# input.net
KiCad netlist of a schematic drawn in Altium Designer
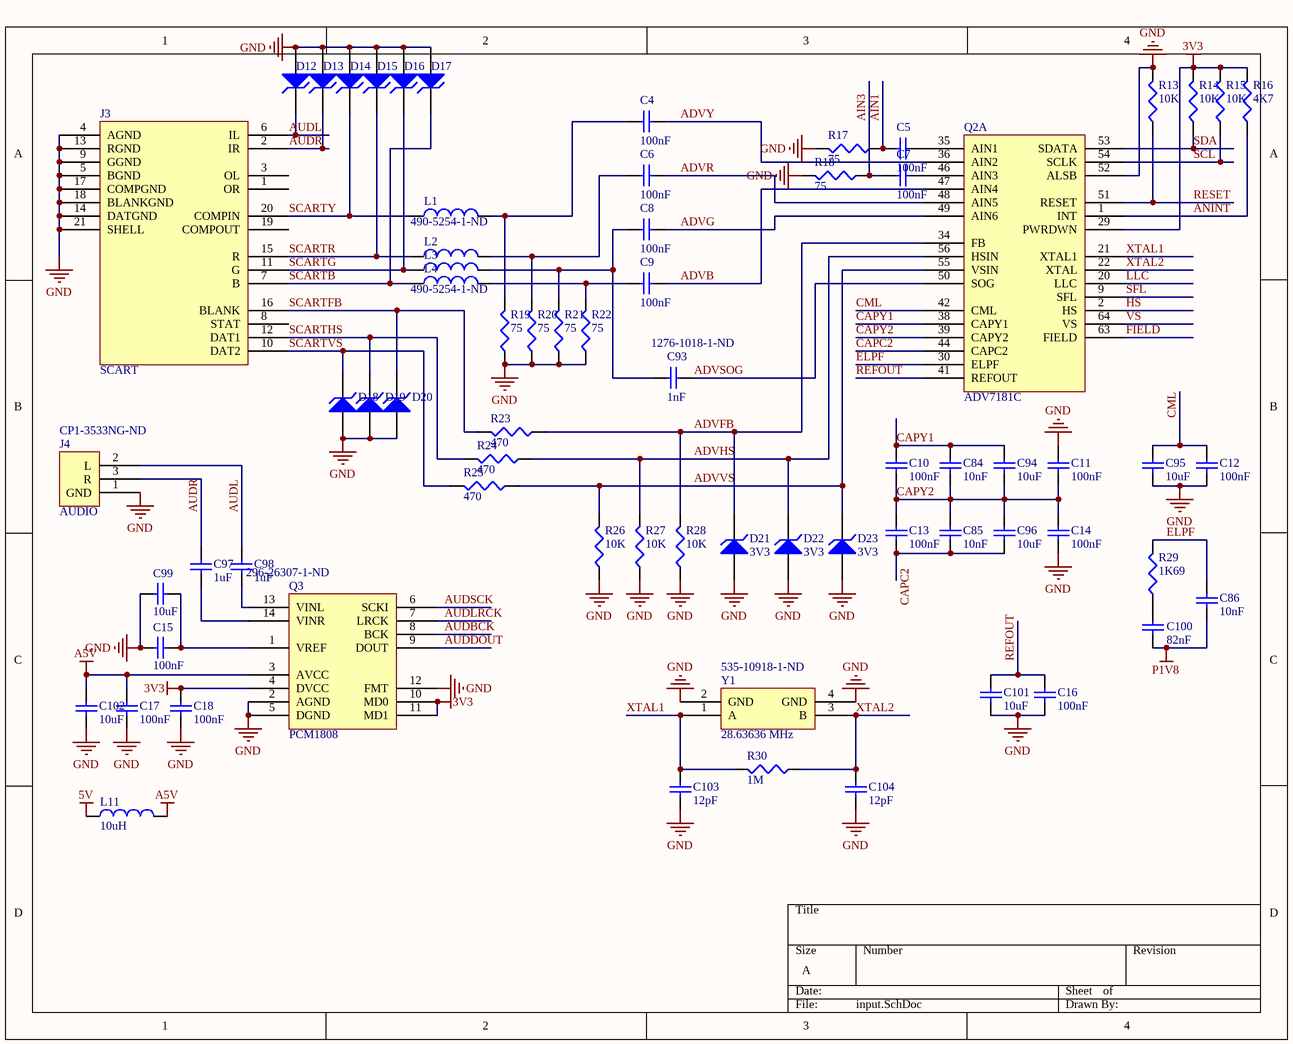
[diagram p0: input.SchDoc]

(export (version "E")
  (design (tool "Eeschema 10.0.6"))
  (components
    (comp (ref "C4")
      (value "100nF")
      (footprint "CAPC1005X06L")
      (description "Capacitor")
      (fields (field (name "Comment") "Cap") (field (name "PUBLISHER") "Altium Limited"))
      (libsource (lib "Miscellaneous Devices") (part "Cap"))
    )
    (comp (ref "C5")
      (value "100nF")
      (footprint "CAPC1005X06L")
      (description "Capacitor")
      (fields (field (name "Comment") "Cap") (field (name "PUBLISHER") "Altium Limited"))
      (libsource (lib "Miscellaneous Devices") (part "Cap"))
    )
    (comp (ref "C6")
      (value "100nF")
      (footprint "CAPC1005X06L")
      (description "Capacitor")
      (fields (field (name "Comment") "Cap") (field (name "PUBLISHER") "Altium Limited"))
      (libsource (lib "Miscellaneous Devices") (part "Cap"))
    )
    (comp (ref "C7")
      (value "100nF")
      (footprint "CAPC1005X06L")
      (description "Capacitor")
      (fields (field (name "Comment") "Cap") (field (name "PUBLISHER") "Altium Limited"))
      (libsource (lib "Miscellaneous Devices") (part "Cap"))
    )
    (comp (ref "C8")
      (value "100nF")
      (footprint "CAPC1005X06L")
      (description "Capacitor")
      (fields (field (name "Comment") "Cap") (field (name "PUBLISHER") "Altium Limited"))
      (libsource (lib "Miscellaneous Devices") (part "Cap"))
    )
    (comp (ref "C9")
      (value "100nF")
      (footprint "CAPC1005X06L")
      (description "Capacitor")
      (fields (field (name "Comment") "Cap") (field (name "PUBLISHER") "Altium Limited"))
      (libsource (lib "Miscellaneous Devices") (part "Cap"))
    )
    (comp (ref "C10")
      (value "100nF")
      (footprint "CAPC1005X06L")
      (description "Capacitor")
      (fields (field (name "Comment") "Cap") (field (name "PUBLISHER") "Altium Limited"))
      (libsource (lib "Miscellaneous Devices") (part "Cap"))
    )
    (comp (ref "C11")
      (value "100nF")
      (footprint "CAPC1005X06L")
      (description "Capacitor")
      (fields (field (name "Comment") "Cap") (field (name "PUBLISHER") "Altium Limited"))
      (libsource (lib "Miscellaneous Devices") (part "Cap"))
    )
    (comp (ref "C12")
      (value "100nF")
      (footprint "CAPC1005X06L")
      (description "Capacitor")
      (fields (field (name "Comment") "Cap") (field (name "PUBLISHER") "Altium Limited"))
      (libsource (lib "Miscellaneous Devices") (part "Cap"))
    )
    (comp (ref "C13")
      (value "100nF")
      (footprint "CAPC1005X06L")
      (description "Capacitor")
      (fields (field (name "Comment") "Cap") (field (name "PUBLISHER") "Altium Limited"))
      (libsource (lib "Miscellaneous Devices") (part "Cap"))
    )
    (comp (ref "C14")
      (value "100nF")
      (footprint "CAPC1005X06L")
      (description "Capacitor")
      (fields (field (name "Comment") "Cap") (field (name "PUBLISHER") "Altium Limited"))
      (libsource (lib "Miscellaneous Devices") (part "Cap"))
    )
    (comp (ref "C15")
      (value "100nF")
      (footprint "CAPC1005X06L")
      (description "Capacitor")
      (fields (field (name "Comment") "Cap") (field (name "PUBLISHER") "Altium Limited"))
      (libsource (lib "Miscellaneous Devices") (part "Cap"))
    )
    (comp (ref "C16")
      (value "100nF")
      (footprint "CAPC1005X06L")
      (description "Capacitor")
      (fields (field (name "Comment") "Cap") (field (name "PUBLISHER") "Altium Limited"))
      (libsource (lib "Miscellaneous Devices") (part "Cap"))
    )
    (comp (ref "C17")
      (value "100nF")
      (footprint "CAPC1005X06L")
      (description "Capacitor")
      (fields (field (name "Comment") "Cap") (field (name "PUBLISHER") "Altium Limited"))
      (libsource (lib "Miscellaneous Devices") (part "Cap"))
    )
    (comp (ref "C18")
      (value "100nF")
      (footprint "CAPC1005X06L")
      (description "Capacitor")
      (fields (field (name "Comment") "Cap") (field (name "PUBLISHER") "Altium Limited"))
      (libsource (lib "Miscellaneous Devices") (part "Cap"))
    )
    (comp (ref "C84")
      (value "10nF")
      (footprint "CAPC1005X06L")
      (description "Capacitor")
      (fields (field (name "Comment") "Cap") (field (name "PUBLISHER") "Altium Limited"))
      (libsource (lib "Miscellaneous Devices") (part "Cap"))
    )
    (comp (ref "C85")
      (value "10nF")
      (footprint "CAPC1005X06L")
      (description "Capacitor")
      (fields (field (name "Comment") "Cap") (field (name "PUBLISHER") "Altium Limited"))
      (libsource (lib "Miscellaneous Devices") (part "Cap"))
    )
    (comp (ref "C86")
      (value "10nF")
      (footprint "CAPC1005X06L")
      (description "Capacitor")
      (fields (field (name "Comment") "Cap") (field (name "PUBLISHER") "Altium Limited"))
      (libsource (lib "Miscellaneous Devices") (part "Cap"))
    )
    (comp (ref "C93")
      (value "1nF")
      (footprint "CAPC1608X90N")
      (description "Capacitor")
      (fields
        (field (name "SUPPLIER PART NUMBER 1") "1276-1018-1-ND")
        (field (name "Comment") "Cap")
        (field (name "PUBLISHER") "Altium Limited")
      )
      (libsource (lib "Miscellaneous Devices") (part "Cap"))
    )
    (comp (ref "C94")
      (value "10uF")
      (footprint "CAPC1608X90N")
      (description "Capacitor")
      (fields (field (name "Comment") "Cap") (field (name "PUBLISHER") "Altium Limited"))
      (libsource (lib "Miscellaneous Devices") (part "Cap"))
    )
    (comp (ref "C95")
      (value "10uF")
      (footprint "CAPC1608X90N")
      (description "Capacitor")
      (fields (field (name "Comment") "Cap") (field (name "PUBLISHER") "Altium Limited"))
      (libsource (lib "Miscellaneous Devices") (part "Cap"))
    )
    (comp (ref "C96")
      (value "10uF")
      (footprint "CAPC1608X90N")
      (description "Capacitor")
      (fields (field (name "Comment") "Cap") (field (name "PUBLISHER") "Altium Limited"))
      (libsource (lib "Miscellaneous Devices") (part "Cap"))
    )
    (comp (ref "C97")
      (value "1uF")
      (footprint "CAPC1608X90N")
      (description "Capacitor")
      (fields (field (name "Comment") "Cap") (field (name "PUBLISHER") "Altium Limited"))
      (libsource (lib "Miscellaneous Devices") (part "Cap"))
    )
    (comp (ref "C98")
      (value "1uF")
      (footprint "CAPC1608X90N")
      (description "Capacitor")
      (fields (field (name "Comment") "Cap") (field (name "PUBLISHER") "Altium Limited"))
      (libsource (lib "Miscellaneous Devices") (part "Cap"))
    )
    (comp (ref "C99")
      (value "10uF")
      (footprint "CAPC1608X90N")
      (description "Capacitor")
      (fields (field (name "Comment") "Cap") (field (name "PUBLISHER") "Altium Limited"))
      (libsource (lib "Miscellaneous Devices") (part "Cap"))
    )
    (comp (ref "C100")
      (value "82nF")
      (footprint "CAPC1608X90N")
      (description "Capacitor")
      (fields (field (name "Comment") "Cap") (field (name "PUBLISHER") "Altium Limited"))
      (libsource (lib "Miscellaneous Devices") (part "Cap"))
    )
    (comp (ref "C101")
      (value "10uF")
      (footprint "CAPC1608X90N")
      (description "Capacitor")
      (fields (field (name "Comment") "Cap") (field (name "PUBLISHER") "Altium Limited"))
      (libsource (lib "Miscellaneous Devices") (part "Cap"))
    )
    (comp (ref "C102")
      (value "10uF")
      (footprint "CAPC1608X90N")
      (description "Capacitor")
      (fields (field (name "Comment") "Cap") (field (name "PUBLISHER") "Altium Limited"))
      (libsource (lib "Miscellaneous Devices") (part "Cap"))
    )
    (comp (ref "C103")
      (value "12pF")
      (footprint "CAPC1608X90N")
      (description "Capacitor")
      (fields (field (name "Comment") "Cap") (field (name "PUBLISHER") "Altium Limited"))
      (libsource (lib "Miscellaneous Devices") (part "Cap"))
    )
    (comp (ref "C104")
      (value "12pF")
      (footprint "CAPC1608X90N")
      (description "Capacitor")
      (fields (field (name "Comment") "Cap") (field (name "PUBLISHER") "Altium Limited"))
      (libsource (lib "Miscellaneous Devices") (part "Cap"))
    )
    (comp (ref "D12")
      (value "EZAEG2A")
      (footprint "CAPC1005X55N")
      (description "Zener Diode")
      (fields (field (name "PUBLISHER") "Altium Limited"))
      (libsource (lib "Miscellaneous Devices") (part "D Zener"))
    )
    (comp (ref "D13")
      (value "EZAEG2A")
      (footprint "CAPC1005X55N")
      (description "Zener Diode")
      (fields (field (name "PUBLISHER") "Altium Limited"))
      (libsource (lib "Miscellaneous Devices") (part "D Zener"))
    )
    (comp (ref "D14")
      (value "EZAEG2A")
      (footprint "CAPC1005X55N")
      (description "Zener Diode")
      (fields (field (name "PUBLISHER") "Altium Limited"))
      (libsource (lib "Miscellaneous Devices") (part "D Zener"))
    )
    (comp (ref "D15")
      (value "EZAEG2A")
      (footprint "CAPC1005X55N")
      (description "Zener Diode")
      (fields (field (name "PUBLISHER") "Altium Limited"))
      (libsource (lib "Miscellaneous Devices") (part "D Zener"))
    )
    (comp (ref "D16")
      (value "EZAEG2A")
      (footprint "CAPC1005X55N")
      (description "Zener Diode")
      (fields (field (name "PUBLISHER") "Altium Limited"))
      (libsource (lib "Miscellaneous Devices") (part "D Zener"))
    )
    (comp (ref "D17")
      (value "EZAEG2A")
      (footprint "CAPC1005X55N")
      (description "Zener Diode")
      (fields (field (name "PUBLISHER") "Altium Limited"))
      (libsource (lib "Miscellaneous Devices") (part "D Zener"))
    )
    (comp (ref "D18")
      (value "EZAEG2A")
      (footprint "CAPC1005X55N")
      (description "Zener Diode")
      (fields (field (name "PUBLISHER") "Altium Limited"))
      (libsource (lib "Miscellaneous Devices") (part "D Zener"))
    )
    (comp (ref "D19")
      (value "EZAEG2A")
      (footprint "CAPC1005X55N")
      (description "Zener Diode")
      (fields (field (name "PUBLISHER") "Altium Limited"))
      (libsource (lib "Miscellaneous Devices") (part "D Zener"))
    )
    (comp (ref "D20")
      (value "EZAEG2A")
      (footprint "CAPC1005X55N")
      (description "Zener Diode")
      (fields (field (name "PUBLISHER") "Altium Limited"))
      (libsource (lib "Miscellaneous Devices") (part "D Zener"))
    )
    (comp (ref "D21")
      (value "3V3")
      (footprint "SOD323")
      (description "Zener Diode")
      (fields (field (name "PUBLISHER") "Altium Limited"))
      (libsource (lib "") (part "D Zener_1"))
    )
    (comp (ref "D22")
      (value "3V3")
      (footprint "SOD323")
      (description "Zener Diode")
      (fields (field (name "PUBLISHER") "Altium Limited"))
      (libsource (lib "") (part "D Zener_1"))
    )
    (comp (ref "D23")
      (value "3V3")
      (footprint "SOD323")
      (description "Zener Diode")
      (fields (field (name "PUBLISHER") "Altium Limited"))
      (libsource (lib "") (part "D Zener_1"))
    )
    (comp (ref "J3") (value "SCART") (footprint "SCART") (libsource (lib "schlib") (part "SCART")))
    (comp (ref "J4")
      (value "AUDIO")
      (footprint "SJ1-3533NG")
      (fields (field (name "SUPPLIER PART NUMBER 1") "CP1-3533NG-ND"))
      (libsource (lib "schlib") (part "AUDIO"))
    )
    (comp (ref "L1")
      (value "~")
      (footprint "CAPC1608X90N")
      (description "Inductor")
      (fields
        (field (name "SUPPLIER PART NUMBER 1") "490-5254-1-ND")
        (field (name "PUBLISHER") "Altium Limited")
      )
      (libsource (lib "Miscellaneous Devices") (part "Inductor"))
    )
    (comp (ref "L2")
      (value "~")
      (footprint "CAPC1608X90N")
      (description "Inductor")
      (fields (field (name "PUBLISHER") "Altium Limited"))
      (libsource (lib "Miscellaneous Devices") (part "Inductor"))
    )
    (comp (ref "L3")
      (value "~")
      (footprint "CAPC1608X90N")
      (description "Inductor")
      (fields (field (name "PUBLISHER") "Altium Limited"))
      (libsource (lib "Miscellaneous Devices") (part "Inductor"))
    )
    (comp (ref "L4")
      (value "~")
      (footprint "CAPC1608X90N")
      (description "Inductor")
      (fields
        (field (name "SUPPLIER PART NUMBER 1") "490-5254-1-ND")
        (field (name "PUBLISHER") "Altium Limited")
      )
      (libsource (lib "Miscellaneous Devices") (part "Inductor"))
    )
    (comp (ref "L11")
      (value "10uH")
      (footprint "CAPC3225X220N")
      (description "Inductor")
      (fields (field (name "Comment") "LBC3225T100KR") (field (name "PUBLISHER") "Altium Limited"))
      (libsource (lib "Miscellaneous Devices") (part "Inductor"))
    )
    (comp (ref "Q2")
      (value "ADV7181C")
      (footprint "TSQFP50P1200X1200X145-64N")
      (libsource (lib "schlib") (part "ADV7181C"))
    )
    (comp (ref "Q3")
      (value "PCM1808")
      (footprint "TSOP65P640X120-14N")
      (fields (field (name "SUPPLIER PART NUMBER 1") "296-26307-1-ND"))
      (libsource (lib "schlib") (part "PCM1808"))
    )
    (comp (ref "R13")
      (value "10K")
      (footprint "CAPC1608X90N")
      (description "Resistor")
      (fields (field (name "Comment") "Res3") (field (name "PUBLISHER") "Altium Limited"))
      (libsource (lib "Miscellaneous Devices") (part "Res3"))
    )
    (comp (ref "R14")
      (value "10K")
      (footprint "CAPC1608X90N")
      (description "Resistor")
      (fields (field (name "Comment") "Res3") (field (name "PUBLISHER") "Altium Limited"))
      (libsource (lib "Miscellaneous Devices") (part "Res3"))
    )
    (comp (ref "R15")
      (value "10K")
      (footprint "CAPC1608X90N")
      (description "Resistor")
      (fields (field (name "Comment") "Res3") (field (name "PUBLISHER") "Altium Limited"))
      (libsource (lib "Miscellaneous Devices") (part "Res3"))
    )
    (comp (ref "R16")
      (value "4K7")
      (footprint "CAPC1608X90N")
      (description "Resistor")
      (fields (field (name "Comment") "Res3") (field (name "PUBLISHER") "Altium Limited"))
      (libsource (lib "Miscellaneous Devices") (part "Res3"))
    )
    (comp (ref "R17")
      (value "75")
      (footprint "CAPC1608X90N")
      (description "Resistor")
      (fields (field (name "Comment") "Res3") (field (name "PUBLISHER") "Altium Limited"))
      (libsource (lib "Miscellaneous Devices") (part "Res3"))
    )
    (comp (ref "R18")
      (value "75")
      (footprint "CAPC1608X90N")
      (description "Resistor")
      (fields (field (name "Comment") "Res3") (field (name "PUBLISHER") "Altium Limited"))
      (libsource (lib "Miscellaneous Devices") (part "Res3"))
    )
    (comp (ref "R19")
      (value "75")
      (footprint "CAPC1608X90N")
      (description "Resistor")
      (fields (field (name "Comment") "Res3") (field (name "PUBLISHER") "Altium Limited"))
      (libsource (lib "Miscellaneous Devices") (part "Res3"))
    )
    (comp (ref "R20")
      (value "75")
      (footprint "CAPC1608X90N")
      (description "Resistor")
      (fields (field (name "Comment") "Res3") (field (name "PUBLISHER") "Altium Limited"))
      (libsource (lib "Miscellaneous Devices") (part "Res3"))
    )
    (comp (ref "R21")
      (value "75")
      (footprint "CAPC1608X90N")
      (description "Resistor")
      (fields (field (name "Comment") "Res3") (field (name "PUBLISHER") "Altium Limited"))
      (libsource (lib "Miscellaneous Devices") (part "Res3"))
    )
    (comp (ref "R22")
      (value "75")
      (footprint "CAPC1608X90N")
      (description "Resistor")
      (fields (field (name "Comment") "Res3") (field (name "PUBLISHER") "Altium Limited"))
      (libsource (lib "Miscellaneous Devices") (part "Res3"))
    )
    (comp (ref "R23")
      (value "470")
      (footprint "CAPC2012X135N")
      (description "Resistor")
      (fields (field (name "Comment") "Res3") (field (name "PUBLISHER") "Altium Limited"))
      (libsource (lib "Miscellaneous Devices") (part "Res3"))
    )
    (comp (ref "R24")
      (value "470")
      (footprint "CAPC2012X135N")
      (description "Resistor")
      (fields (field (name "Comment") "Res3") (field (name "PUBLISHER") "Altium Limited"))
      (libsource (lib "Miscellaneous Devices") (part "Res3"))
    )
    (comp (ref "R25")
      (value "470")
      (footprint "CAPC2012X135N")
      (description "Resistor")
      (fields (field (name "Comment") "Res3") (field (name "PUBLISHER") "Altium Limited"))
      (libsource (lib "Miscellaneous Devices") (part "Res3"))
    )
    (comp (ref "R26")
      (value "10K")
      (footprint "CAPC1608X90N")
      (description "Resistor")
      (fields (field (name "Comment") "Res3") (field (name "PUBLISHER") "Altium Limited"))
      (libsource (lib "Miscellaneous Devices") (part "Res3"))
    )
    (comp (ref "R27")
      (value "10K")
      (footprint "CAPC1608X90N")
      (description "Resistor")
      (fields (field (name "Comment") "Res3") (field (name "PUBLISHER") "Altium Limited"))
      (libsource (lib "Miscellaneous Devices") (part "Res3"))
    )
    (comp (ref "R28")
      (value "10K")
      (footprint "CAPC1608X90N")
      (description "Resistor")
      (fields (field (name "Comment") "Res3") (field (name "PUBLISHER") "Altium Limited"))
      (libsource (lib "Miscellaneous Devices") (part "Res3"))
    )
    (comp (ref "R29")
      (value "1K69")
      (footprint "CAPC1608X90N")
      (description "Resistor")
      (fields (field (name "Comment") "Res3") (field (name "PUBLISHER") "Altium Limited"))
      (libsource (lib "Miscellaneous Devices") (part "Res3"))
    )
    (comp (ref "R30")
      (value "1M")
      (footprint "CAPC1608X90N")
      (description "Resistor")
      (fields (field (name "Comment") "Res3") (field (name "PUBLISHER") "Altium Limited"))
      (libsource (lib "Miscellaneous Devices") (part "Res3"))
    )
    (comp (ref "Y1")
      (value "28.63636 MHz")
      (footprint "ABM8G")
      (fields (field (name "SUPPLIER PART NUMBER 1") "535-10918-1-ND"))
      (libsource (lib "schlib") (part "XTAL"))
    )
  )
  (nets
    (net (code "1") (name "/ADVB") (class "Default")
      (node (ref "C9") (pin "2") (pinfunction "2_2") (pintype "passive"))
      (node (ref "Q2") (pin "47") (pinfunction "AIN4_47") (pintype "passive"))
    )
    (net (code "2") (name "/ADVFB") (class "Default")
      (node (ref "D21") (pin "K") (pinfunction "K_K") (pintype "passive"))
      (node (ref "Q2") (pin "34") (pinfunction "FB_34") (pintype "passive"))
      (node (ref "R23") (pin "1") (pinfunction "1_1") (pintype "passive"))
      (node (ref "R28") (pin "2") (pinfunction "2_2") (pintype "passive"))
    )
    (net (code "3") (name "/ADVG") (class "Default")
      (node (ref "C8") (pin "2") (pinfunction "2_2") (pintype "passive"))
      (node (ref "Q2") (pin "49") (pinfunction "AIN6_49") (pintype "passive"))
    )
    (net (code "4") (name "/ADVHS") (class "Default")
      (node (ref "D22") (pin "K") (pinfunction "K_K") (pintype "passive"))
      (node (ref "Q2") (pin "56") (pinfunction "HSIN_56") (pintype "passive"))
      (node (ref "R24") (pin "1") (pinfunction "1_1") (pintype "passive"))
      (node (ref "R27") (pin "2") (pinfunction "2_2") (pintype "passive"))
    )
    (net (code "5") (name "/ADVR") (class "Default")
      (node (ref "C6") (pin "2") (pinfunction "2_2") (pintype "passive"))
      (node (ref "Q2") (pin "48") (pinfunction "AIN5_48") (pintype "passive"))
    )
    (net (code "6") (name "/ADVSOG") (class "Default")
      (node (ref "C93") (pin "2") (pinfunction "2_2") (pintype "passive"))
      (node (ref "Q2") (pin "50") (pinfunction "SOG_50") (pintype "passive"))
    )
    (net (code "7") (name "/ADVVS") (class "Default")
      (node (ref "D23") (pin "K") (pinfunction "K_K") (pintype "passive"))
      (node (ref "Q2") (pin "55") (pinfunction "VSIN_55") (pintype "passive"))
      (node (ref "R25") (pin "1") (pinfunction "1_1") (pintype "passive"))
      (node (ref "R26") (pin "2") (pinfunction "2_2") (pintype "passive"))
    )
    (net (code "8") (name "/ADVY") (class "Default")
      (node (ref "C4") (pin "2") (pinfunction "2_2") (pintype "passive"))
      (node (ref "Q2") (pin "36") (pinfunction "AIN2_36") (pintype "passive"))
    )
    (net (code "9") (name "/AIN1") (class "Default")
      (node (ref "C5") (pin "1") (pinfunction "1_1") (pintype "passive"))
      (node (ref "R17") (pin "1") (pinfunction "1_1") (pintype "passive"))
    )
    (net (code "10") (name "/AIN3") (class "Default")
      (node (ref "C7") (pin "1") (pinfunction "1_1") (pintype "passive"))
      (node (ref "R18") (pin "1") (pinfunction "1_1") (pintype "passive"))
    )
    (net (code "11") (name "/ANINT") (class "Default")
      (node (ref "Q2") (pin "1") (pinfunction "INT_1") (pintype "passive"))
      (node (ref "R16") (pin "1") (pinfunction "1_1") (pintype "passive"))
    )
    (net (code "12") (name "/AUDBCK") (class "Default")
      (node (ref "Q3") (pin "8") (pinfunction "BCK_8") (pintype "passive"))
    )
    (net (code "13") (name "/AUDDOUT") (class "Default")
      (node (ref "Q3") (pin "9") (pinfunction "DOUT_9") (pintype "passive"))
    )
    (net (code "14") (name "/AUDL") (class "Default")
      (node (ref "C98") (pin "1") (pinfunction "1_1") (pintype "passive"))
      (node (ref "D12") (pin "2") (pinfunction "K_2") (pintype "passive"))
      (node (ref "J3") (pin "6") (pinfunction "IL_6") (pintype "passive"))
      (node (ref "J4") (pin "2") (pinfunction "L_2") (pintype "passive"))
    )
    (net (code "15") (name "/AUDLRCK") (class "Default")
      (node (ref "Q3") (pin "7") (pinfunction "LRCK_7") (pintype "passive"))
    )
    (net (code "16") (name "/AUDR") (class "Default")
      (node (ref "C97") (pin "1") (pinfunction "1_1") (pintype "passive"))
      (node (ref "D13") (pin "2") (pinfunction "K_2") (pintype "passive"))
      (node (ref "J3") (pin "2") (pinfunction "IR_2") (pintype "passive"))
      (node (ref "J4") (pin "3") (pinfunction "R_3") (pintype "passive"))
    )
    (net (code "17") (name "/AUDSCK") (class "Default")
      (node (ref "Q3") (pin "6") (pinfunction "SCKI_6") (pintype "passive"))
    )
    (net (code "18") (name "/CAPC2") (class "Default")
      (node (ref "C13") (pin "1") (pinfunction "1_1") (pintype "passive"))
      (node (ref "C85") (pin "1") (pinfunction "1_1") (pintype "passive"))
      (node (ref "C96") (pin "1") (pinfunction "1_1") (pintype "passive"))
      (node (ref "Q2") (pin "44") (pinfunction "CAPC2_44") (pintype "passive"))
    )
    (net (code "19") (name "/CAPY1") (class "Default")
      (node (ref "C10") (pin "2") (pinfunction "2_2") (pintype "passive"))
      (node (ref "C84") (pin "2") (pinfunction "2_2") (pintype "passive"))
      (node (ref "C94") (pin "2") (pinfunction "2_2") (pintype "passive"))
      (node (ref "Q2") (pin "38") (pinfunction "CAPY1_38") (pintype "passive"))
    )
    (net (code "20") (name "/CAPY2") (class "Default")
      (node (ref "C10") (pin "1") (pinfunction "1_1") (pintype "passive"))
      (node (ref "C11") (pin "1") (pinfunction "1_1") (pintype "passive"))
      (node (ref "C13") (pin "2") (pinfunction "2_2") (pintype "passive"))
      (node (ref "C14") (pin "2") (pinfunction "2_2") (pintype "passive"))
      (node (ref "C84") (pin "1") (pinfunction "1_1") (pintype "passive"))
      (node (ref "C85") (pin "2") (pinfunction "2_2") (pintype "passive"))
      (node (ref "C94") (pin "1") (pinfunction "1_1") (pintype "passive"))
      (node (ref "C96") (pin "2") (pinfunction "2_2") (pintype "passive"))
      (node (ref "Q2") (pin "39") (pinfunction "CAPY2_39") (pintype "passive"))
    )
    (net (code "21") (name "/CML") (class "Default")
      (node (ref "C12") (pin "2") (pinfunction "2_2") (pintype "passive"))
      (node (ref "C95") (pin "2") (pinfunction "2_2") (pintype "passive"))
      (node (ref "Q2") (pin "42") (pinfunction "CML_42") (pintype "passive"))
    )
    (net (code "22") (name "/ELPF") (class "Default")
      (node (ref "C86") (pin "2") (pinfunction "2_2") (pintype "passive"))
      (node (ref "Q2") (pin "30") (pinfunction "ELPF_30") (pintype "passive"))
      (node (ref "R29") (pin "2") (pinfunction "2_2") (pintype "passive"))
    )
    (net (code "23") (name "/FIELD") (class "Default")
      (node (ref "Q2") (pin "63") (pinfunction "FIELD_63") (pintype "passive"))
    )
    (net (code "24") (name "/HS") (class "Default")
      (node (ref "Q2") (pin "2") (pinfunction "HS_2") (pintype "passive"))
    )
    (net (code "25") (name "/LLC") (class "Default")
      (node (ref "Q2") (pin "20") (pinfunction "LLC_20") (pintype "passive"))
    )
    (net (code "26") (name "/REFOUT") (class "Default")
      (node (ref "C101") (pin "2") (pinfunction "2_2") (pintype "passive"))
      (node (ref "C16") (pin "2") (pinfunction "2_2") (pintype "passive"))
      (node (ref "Q2") (pin "41") (pinfunction "REFOUT_41") (pintype "passive"))
    )
    (net (code "27") (name "/RESET") (class "Default")
      (node (ref "Q2") (pin "51") (pinfunction "RESET_51") (pintype "passive"))
      (node (ref "R13") (pin "1") (pinfunction "1_1") (pintype "passive"))
    )
    (net (code "28") (name "/SCARTB") (class "Default")
      (node (ref "D17") (pin "2") (pinfunction "K_2") (pintype "passive"))
      (node (ref "J3") (pin "7") (pinfunction "B_7") (pintype "passive"))
      (node (ref "L4") (pin "1") (pinfunction "1_1") (pintype "passive"))
    )
    (net (code "29") (name "/SCARTFB") (class "Default")
      (node (ref "D20") (pin "2") (pinfunction "K_2") (pintype "passive"))
      (node (ref "J3") (pin "16") (pinfunction "BLANK_16") (pintype "passive"))
      (node (ref "R23") (pin "2") (pinfunction "2_2") (pintype "passive"))
    )
    (net (code "30") (name "/SCARTG") (class "Default")
      (node (ref "D16") (pin "2") (pinfunction "K_2") (pintype "passive"))
      (node (ref "J3") (pin "11") (pinfunction "G_11") (pintype "passive"))
      (node (ref "L3") (pin "1") (pinfunction "1_1") (pintype "passive"))
    )
    (net (code "31") (name "/SCARTHS") (class "Default")
      (node (ref "D19") (pin "2") (pinfunction "K_2") (pintype "passive"))
      (node (ref "J3") (pin "12") (pinfunction "DAT1_12") (pintype "passive"))
      (node (ref "R24") (pin "2") (pinfunction "2_2") (pintype "passive"))
    )
    (net (code "32") (name "/SCARTR") (class "Default")
      (node (ref "D15") (pin "2") (pinfunction "K_2") (pintype "passive"))
      (node (ref "J3") (pin "15") (pinfunction "R_15") (pintype "passive"))
      (node (ref "L2") (pin "1") (pinfunction "1_1") (pintype "passive"))
    )
    (net (code "33") (name "/SCARTVS") (class "Default")
      (node (ref "D18") (pin "2") (pinfunction "K_2") (pintype "passive"))
      (node (ref "J3") (pin "10") (pinfunction "DAT2_10") (pintype "passive"))
      (node (ref "R25") (pin "2") (pinfunction "2_2") (pintype "passive"))
    )
    (net (code "34") (name "/SCARTY") (class "Default")
      (node (ref "D14") (pin "2") (pinfunction "K_2") (pintype "passive"))
      (node (ref "J3") (pin "20") (pinfunction "COMPIN_20") (pintype "passive"))
      (node (ref "L1") (pin "1") (pinfunction "1_1") (pintype "passive"))
    )
    (net (code "35") (name "/SCL") (class "Default")
      (node (ref "Q2") (pin "54") (pinfunction "SCLK_54") (pintype "passive"))
      (node (ref "R15") (pin "1") (pinfunction "1_1") (pintype "passive"))
    )
    (net (code "36") (name "/SDA") (class "Default")
      (node (ref "Q2") (pin "53") (pinfunction "SDATA_53") (pintype "passive"))
      (node (ref "R14") (pin "1") (pinfunction "1_1") (pintype "passive"))
    )
    (net (code "37") (name "/SFL") (class "Default")
      (node (ref "Q2") (pin "9") (pinfunction "SFL_9") (pintype "passive"))
    )
    (net (code "38") (name "/VS") (class "Default")
      (node (ref "Q2") (pin "64") (pinfunction "VS_64") (pintype "passive"))
    )
    (net (code "39") (name "/XTAL1") (class "Default")
      (node (ref "C103") (pin "2") (pinfunction "2_2") (pintype "passive"))
      (node (ref "Q2") (pin "21") (pinfunction "XTAL1_21") (pintype "passive"))
      (node (ref "R30") (pin "2") (pinfunction "2_2") (pintype "passive"))
      (node (ref "Y1") (pin "1") (pinfunction "A_1") (pintype "passive"))
    )
    (net (code "40") (name "/XTAL2") (class "Default")
      (node (ref "C104") (pin "2") (pinfunction "2_2") (pintype "passive"))
      (node (ref "Q2") (pin "22") (pinfunction "XTAL_22") (pintype "passive"))
      (node (ref "R30") (pin "1") (pinfunction "1_1") (pintype "passive"))
      (node (ref "Y1") (pin "3") (pinfunction "B_3") (pintype "passive"))
    )
    (net (code "41") (name "3V3") (class "Default")
      (node (ref "C18") (pin "1") (pinfunction "1_1") (pintype "passive"))
      (node (ref "Q2") (pin "29") (pinfunction "PWRDWN_29") (pintype "passive"))
      (node (ref "Q3") (pin "10") (pinfunction "MD0_10") (pintype "passive"))
      (node (ref "Q3") (pin "11") (pinfunction "MD1_11") (pintype "passive"))
      (node (ref "Q3") (pin "4") (pinfunction "DVCC_4") (pintype "passive"))
      (node (ref "R14") (pin "2") (pinfunction "2_2") (pintype "passive"))
      (node (ref "R15") (pin "2") (pinfunction "2_2") (pintype "passive"))
      (node (ref "R16") (pin "2") (pinfunction "2_2") (pintype "passive"))
    )
    (net (code "42") (name "5V") (class "Default")
      (node (ref "L11") (pin "1") (pinfunction "1_1") (pintype "passive"))
    )
    (net (code "43") (name "A5V") (class "Default")
      (node (ref "C102") (pin "1") (pinfunction "1_1") (pintype "passive"))
      (node (ref "C17") (pin "1") (pinfunction "1_1") (pintype "passive"))
      (node (ref "L11") (pin "2") (pinfunction "2_2") (pintype "passive"))
      (node (ref "Q3") (pin "3") (pinfunction "AVCC_3") (pintype "passive"))
    )
    (net (code "44") (name "GND") (class "Default")
      (node (ref "C101") (pin "1") (pinfunction "1_1") (pintype "passive"))
      (node (ref "C102") (pin "2") (pinfunction "2_2") (pintype "passive"))
      (node (ref "C103") (pin "1") (pinfunction "1_1") (pintype "passive"))
      (node (ref "C104") (pin "1") (pinfunction "1_1") (pintype "passive"))
      (node (ref "C11") (pin "2") (pinfunction "2_2") (pintype "passive"))
      (node (ref "C12") (pin "1") (pinfunction "1_1") (pintype "passive"))
      (node (ref "C14") (pin "1") (pinfunction "1_1") (pintype "passive"))
      (node (ref "C15") (pin "2") (pinfunction "2_2") (pintype "passive"))
      (node (ref "C16") (pin "1") (pinfunction "1_1") (pintype "passive"))
      (node (ref "C17") (pin "2") (pinfunction "2_2") (pintype "passive"))
      (node (ref "C18") (pin "2") (pinfunction "2_2") (pintype "passive"))
      (node (ref "C95") (pin "1") (pinfunction "1_1") (pintype "passive"))
      (node (ref "C99") (pin "2") (pinfunction "2_2") (pintype "passive"))
      (node (ref "D12") (pin "1") (pinfunction "A_1") (pintype "passive"))
      (node (ref "D13") (pin "1") (pinfunction "A_1") (pintype "passive"))
      (node (ref "D14") (pin "1") (pinfunction "A_1") (pintype "passive"))
      (node (ref "D15") (pin "1") (pinfunction "A_1") (pintype "passive"))
      (node (ref "D16") (pin "1") (pinfunction "A_1") (pintype "passive"))
      (node (ref "D17") (pin "1") (pinfunction "A_1") (pintype "passive"))
      (node (ref "D18") (pin "1") (pinfunction "A_1") (pintype "passive"))
      (node (ref "D19") (pin "1") (pinfunction "A_1") (pintype "passive"))
      (node (ref "D20") (pin "1") (pinfunction "A_1") (pintype "passive"))
      (node (ref "D21") (pin "A") (pinfunction "A_A") (pintype "passive"))
      (node (ref "D22") (pin "A") (pinfunction "A_A") (pintype "passive"))
      (node (ref "D23") (pin "A") (pinfunction "A_A") (pintype "passive"))
      (node (ref "J3") (pin "13") (pinfunction "RGND_13") (pintype "passive"))
      (node (ref "J3") (pin "14") (pinfunction "DATGND_14") (pintype "passive"))
      (node (ref "J3") (pin "17") (pinfunction "COMPGND_17") (pintype "passive"))
      (node (ref "J3") (pin "18") (pinfunction "BLANKGND_18") (pintype "passive"))
      (node (ref "J3") (pin "21") (pinfunction "SHELL_21") (pintype "passive"))
      (node (ref "J3") (pin "4") (pinfunction "AGND_4") (pintype "passive"))
      (node (ref "J3") (pin "5") (pinfunction "BGND_5") (pintype "passive"))
      (node (ref "J3") (pin "9") (pinfunction "GGND_9") (pintype "passive"))
      (node (ref "J4") (pin "1") (pinfunction "GND_1") (pintype "passive"))
      (node (ref "Q2") (pin "52") (pinfunction "ALSB_52") (pintype "passive"))
      (node (ref "Q3") (pin "12") (pinfunction "FMT_12") (pintype "passive"))
      (node (ref "Q3") (pin "2") (pinfunction "AGND_2") (pintype "passive"))
      (node (ref "Q3") (pin "5") (pinfunction "DGND_5") (pintype "passive"))
      (node (ref "R13") (pin "2") (pinfunction "2_2") (pintype "passive"))
      (node (ref "R17") (pin "2") (pinfunction "2_2") (pintype "passive"))
      (node (ref "R18") (pin "2") (pinfunction "2_2") (pintype "passive"))
      (node (ref "R19") (pin "1") (pinfunction "1_1") (pintype "passive"))
      (node (ref "R20") (pin "1") (pinfunction "1_1") (pintype "passive"))
      (node (ref "R21") (pin "1") (pinfunction "1_1") (pintype "passive"))
      (node (ref "R22") (pin "1") (pinfunction "1_1") (pintype "passive"))
      (node (ref "R26") (pin "1") (pinfunction "1_1") (pintype "passive"))
      (node (ref "R27") (pin "1") (pinfunction "1_1") (pintype "passive"))
      (node (ref "R28") (pin "1") (pinfunction "1_1") (pintype "passive"))
      (node (ref "Y1") (pin "2") (pinfunction "GND_2") (pintype "passive"))
      (node (ref "Y1") (pin "4") (pinfunction "GND_4") (pintype "passive"))
    )
    (net (code "45") (name "Net-(C4-Pad1)") (class "Default")
      (node (ref "C4") (pin "1") (pinfunction "1_1") (pintype "passive"))
      (node (ref "L1") (pin "2") (pinfunction "2_2") (pintype "passive"))
      (node (ref "R19") (pin "2") (pinfunction "2_2") (pintype "passive"))
    )
    (net (code "46") (name "Net-(C6-Pad1)") (class "Default")
      (node (ref "C6") (pin "1") (pinfunction "1_1") (pintype "passive"))
      (node (ref "L2") (pin "2") (pinfunction "2_2") (pintype "passive"))
      (node (ref "R20") (pin "2") (pinfunction "2_2") (pintype "passive"))
    )
    (net (code "47") (name "Net-(C8-Pad1)") (class "Default")
      (node (ref "C8") (pin "1") (pinfunction "1_1") (pintype "passive"))
      (node (ref "C93") (pin "1") (pinfunction "1_1") (pintype "passive"))
      (node (ref "L3") (pin "2") (pinfunction "2_2") (pintype "passive"))
      (node (ref "R21") (pin "2") (pinfunction "2_2") (pintype "passive"))
    )
    (net (code "48") (name "Net-(C9-Pad1)") (class "Default")
      (node (ref "C9") (pin "1") (pinfunction "1_1") (pintype "passive"))
      (node (ref "L4") (pin "2") (pinfunction "2_2") (pintype "passive"))
      (node (ref "R22") (pin "2") (pinfunction "2_2") (pintype "passive"))
    )
    (net (code "49") (name "Net-(C100-Pad2)") (class "Default")
      (node (ref "C100") (pin "2") (pinfunction "2_2") (pintype "passive"))
      (node (ref "R29") (pin "1") (pinfunction "1_1") (pintype "passive"))
    )
    (net (code "50") (name "Net-(Q2A-AIN1)") (class "Default")
      (node (ref "C5") (pin "2") (pinfunction "2_2") (pintype "passive"))
      (node (ref "Q2") (pin "35") (pinfunction "AIN1_35") (pintype "passive"))
    )
    (net (code "51") (name "Net-(Q2A-AIN3)") (class "Default")
      (node (ref "C7") (pin "2") (pinfunction "2_2") (pintype "passive"))
      (node (ref "Q2") (pin "46") (pinfunction "AIN3_46") (pintype "passive"))
    )
    (net (code "52") (name "Net-(Q3-VINL)") (class "Default")
      (node (ref "C98") (pin "2") (pinfunction "2_2") (pintype "passive"))
      (node (ref "Q3") (pin "13") (pinfunction "VINL_13") (pintype "passive"))
    )
    (net (code "53") (name "Net-(Q3-VINR)") (class "Default")
      (node (ref "C97") (pin "2") (pinfunction "2_2") (pintype "passive"))
      (node (ref "Q3") (pin "14") (pinfunction "VINR_14") (pintype "passive"))
    )
    (net (code "54") (name "Net-(Q3-VREF)") (class "Default")
      (node (ref "C15") (pin "1") (pinfunction "1_1") (pintype "passive"))
      (node (ref "C99") (pin "1") (pinfunction "1_1") (pintype "passive"))
      (node (ref "Q3") (pin "1") (pinfunction "VREF_1") (pintype "passive"))
    )
    (net (code "55") (name "P1V8") (class "Default")
      (node (ref "C100") (pin "1") (pinfunction "1_1") (pintype "passive"))
      (node (ref "C86") (pin "1") (pinfunction "1_1") (pintype "passive"))
    )
    (net (code "56") (name "unconnected-(J3-COMPOUT-Pad19)") (class "Default")
      (node (ref "J3") (pin "19") (pinfunction "COMPOUT_19") (pintype "passive"))
    )
    (net (code "57") (name "unconnected-(J3-OL-Pad3)") (class "Default")
      (node (ref "J3") (pin "3") (pinfunction "OL_3") (pintype "passive"))
    )
    (net (code "58") (name "unconnected-(J3-OR-Pad1)") (class "Default")
      (node (ref "J3") (pin "1") (pinfunction "OR_1") (pintype "passive"))
    )
    (net (code "59") (name "unconnected-(J3-STAT-Pad8)") (class "Default")
      (node (ref "J3") (pin "8") (pinfunction "STAT_8") (pintype "passive"))
    )
  )
)
